# design.net
KiCad netlist of a schematic drawn in Altium Designer
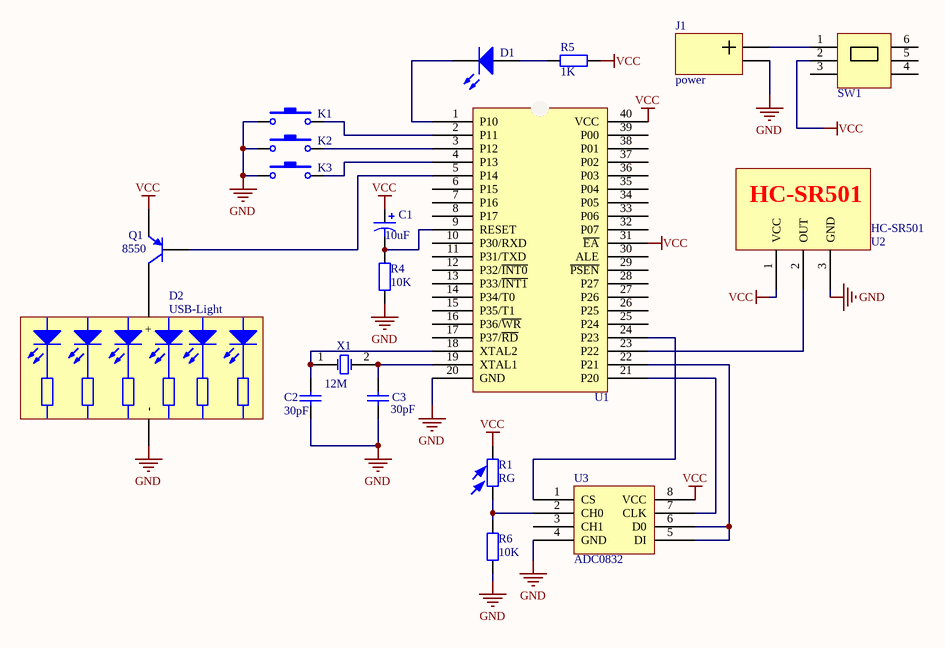
[diagram p0: 原理图.SCHDOC]

(export (version "E")
  (design (tool "Eeschema 10.0.6"))
  (components
    (comp (ref "C1") (value "10uF") (footprint "CAP_2") (libsource (lib "Schlib") (part "CAP_2")))
    (comp (ref "C2") (value "30pF") (footprint "CAP") (libsource (lib "Schlib") (part "CAP")))
    (comp (ref "C3") (value "30pF") (footprint "CAP") (libsource (lib "Schlib") (part "CAP")))
    (comp (ref "D1") (value "~") (footprint "LED") (libsource (lib "MANUAL") (part "LED")))
    (comp (ref "D2")
      (value "USB-Light")
      (footprint "USB-A - 2")
      (libsource (lib "MANUAL") (part "USB-Light"))
    )
    (comp (ref "J1") (value "power") (footprint "DC3.5") (libsource (lib "Schlib") (part "DC5.5")))
    (comp (ref "K1") (value "KEY") (footprint "KEY") (libsource (lib "Schlib") (part "KEY")))
    (comp (ref "K2") (value "KEY") (footprint "KEY") (libsource (lib "Schlib") (part "KEY")))
    (comp (ref "K3") (value "KEY") (footprint "KEY") (libsource (lib "Schlib") (part "KEY")))
    (comp (ref "Q1") (value "8550") (footprint "NPN") (libsource (lib "Schlib") (part "PNP")))
    (comp (ref "R1") (value "RG") (libsource (lib "MANUAL") (part "RG")))
    (comp (ref "R4") (value "10K") (footprint "RES") (libsource (lib "Schlib") (part "Res")))
    (comp (ref "R5") (value "1K") (footprint "RES") (libsource (lib "MANUAL") (part "Res")))
    (comp (ref "R6") (value "10K") (footprint "RES") (libsource (lib "") (part "Res_1")))
    (comp (ref "SW1") (value "SWT") (footprint "SWT") (libsource (lib "Schlib") (part "SWT")))
    (comp (ref "U1") (value "STC89C52") (footprint "DIP40") (libsource (lib "Schlib") (part "STC89C52")))
    (comp (ref "U2") (value "HC-SR501") (footprint "HC-SR501") (libsource (lib "MANUAL") (part "HC-SR501")))
    (comp (ref "U3") (value "ADC0832") (footprint "DIP8") (libsource (lib "MANUAL") (part "ADC0832")))
    (comp (ref "X1") (value "12M") (footprint "XTAL") (libsource (lib "Schlib") (part "XTAL")))
  )
  (nets
    (net (code "1") (name "GND") (class "Default")
      (node (ref "C2") (pin "1") (pinfunction "1_1") (pintype "passive"))
      (node (ref "C3") (pin "1") (pinfunction "1_1") (pintype "passive"))
      (node (ref "D2") (pin "2") (pinfunction "-_2") (pintype "passive"))
      (node (ref "J1") (pin "2") (pinfunction "2_2") (pintype "passive"))
      (node (ref "K1") (pin "1") (pinfunction "1_1") (pintype "passive"))
      (node (ref "K2") (pin "1") (pinfunction "1_1") (pintype "passive"))
      (node (ref "K3") (pin "1") (pinfunction "1_1") (pintype "passive"))
      (node (ref "R4") (pin "1") (pinfunction "1_1") (pintype "passive"))
      (node (ref "R6") (pin "1") (pinfunction "1_1") (pintype "passive"))
      (node (ref "U1") (pin "20") (pinfunction "GND_20") (pintype "passive"))
      (node (ref "U2") (pin "3") (pinfunction "GND_3") (pintype "passive"))
      (node (ref "U3") (pin "4") (pinfunction "GND_4") (pintype "passive"))
    )
    (net (code "2") (name "Net-(D1-Pad1)") (class "Default")
      (node (ref "D1") (pin "1") (pinfunction "1_1") (pintype "passive"))
      (node (ref "R5") (pin "1") (pinfunction "1_1") (pintype "passive"))
    )
    (net (code "3") (name "Net-(D2-+)") (class "Default")
      (node (ref "D2") (pin "1") (pinfunction "+_1") (pintype "passive"))
      (node (ref "Q1") (pin "C") (pinfunction "C_C") (pintype "passive"))
    )
    (net (code "4") (name "Net-(SW1-0)") (class "Default")
      (node (ref "J1") (pin "1") (pinfunction "1_1") (pintype "passive"))
      (node (ref "SW1") (pin "1") (pinfunction "0_1") (pintype "passive"))
    )
    (net (code "5") (name "Net-(U1-P10)") (class "Default")
      (node (ref "D1") (pin "2") (pinfunction "2_2") (pintype "passive"))
      (node (ref "U1") (pin "1") (pinfunction "P10_1") (pintype "passive"))
    )
    (net (code "6") (name "Net-(U1-P11)") (class "Default")
      (node (ref "K1") (pin "2") (pinfunction "2_2") (pintype "passive"))
      (node (ref "U1") (pin "2") (pinfunction "P11_2") (pintype "passive"))
    )
    (net (code "7") (name "Net-(U1-P12)") (class "Default")
      (node (ref "K2") (pin "2") (pinfunction "2_2") (pintype "passive"))
      (node (ref "U1") (pin "3") (pinfunction "P12_3") (pintype "passive"))
    )
    (net (code "8") (name "Net-(U1-P13)") (class "Default")
      (node (ref "K3") (pin "2") (pinfunction "2_2") (pintype "passive"))
      (node (ref "U1") (pin "4") (pinfunction "P13_4") (pintype "passive"))
    )
    (net (code "9") (name "Net-(U1-P14)") (class "Default")
      (node (ref "Q1") (pin "B") (pinfunction "B_B") (pintype "passive"))
      (node (ref "U1") (pin "5") (pinfunction "P14_5") (pintype "passive"))
    )
    (net (code "10") (name "Net-(U1-P20)") (class "Default")
      (node (ref "U1") (pin "21") (pinfunction "P20_21") (pintype "passive"))
      (node (ref "U3") (pin "7") (pinfunction "CLK_7") (pintype "passive"))
    )
    (net (code "11") (name "Net-(U1-P21)") (class "Default")
      (node (ref "U1") (pin "22") (pinfunction "P21_22") (pintype "passive"))
      (node (ref "U3") (pin "5") (pinfunction "DI_5") (pintype "passive"))
      (node (ref "U3") (pin "6") (pinfunction "D0_6") (pintype "passive"))
    )
    (net (code "12") (name "Net-(U1-P22)") (class "Default")
      (node (ref "U1") (pin "23") (pinfunction "P22_23") (pintype "passive"))
      (node (ref "U2") (pin "2") (pinfunction "OUT_2") (pintype "passive"))
    )
    (net (code "13") (name "Net-(U1-P23)") (class "Default")
      (node (ref "U1") (pin "24") (pinfunction "P23_24") (pintype "passive"))
      (node (ref "U3") (pin "1") (pinfunction "CS_1") (pintype "passive"))
    )
    (net (code "14") (name "Net-(U1-RESET)") (class "Default")
      (node (ref "C1") (pin "2") (pinfunction "2_2") (pintype "passive"))
      (node (ref "R4") (pin "2") (pinfunction "2_2") (pintype "passive"))
      (node (ref "U1") (pin "9") (pinfunction "RESET_9") (pintype "passive"))
    )
    (net (code "15") (name "Net-(U1-XTAL1)") (class "Default")
      (node (ref "C3") (pin "2") (pinfunction "2_2") (pintype "passive"))
      (node (ref "U1") (pin "19") (pinfunction "XTAL1_19") (pintype "passive"))
      (node (ref "X1") (pin "2") (pinfunction "OSC2_2") (pintype "passive"))
    )
    (net (code "16") (name "Net-(U1-XTAL2)") (class "Default")
      (node (ref "C2") (pin "2") (pinfunction "2_2") (pintype "passive"))
      (node (ref "U1") (pin "18") (pinfunction "XTAL2_18") (pintype "passive"))
      (node (ref "X1") (pin "1") (pinfunction "OSC1_1") (pintype "passive"))
    )
    (net (code "17") (name "Net-(U3-CH0)") (class "Default")
      (node (ref "R1") (pin "1") (pinfunction "1_1") (pintype "passive"))
      (node (ref "R6") (pin "2") (pinfunction "2_2") (pintype "passive"))
      (node (ref "U3") (pin "2") (pinfunction "CH0_2") (pintype "passive"))
    )
    (net (code "18") (name "VCC") (class "Default")
      (node (ref "C1") (pin "1") (pinfunction "1_1") (pintype "passive"))
      (node (ref "Q1") (pin "E") (pinfunction "E_E") (pintype "passive"))
      (node (ref "R1") (pin "2") (pinfunction "2_2") (pintype "passive"))
      (node (ref "R5") (pin "2") (pinfunction "2_2") (pintype "passive"))
      (node (ref "SW1") (pin "2") (pinfunction "1_2") (pintype "passive"))
      (node (ref "U1") (pin "31") (pinfunction "~{EA}_31") (pintype "passive"))
      (node (ref "U1") (pin "40") (pinfunction "VCC_40") (pintype "passive"))
      (node (ref "U2") (pin "1") (pinfunction "VCC_1") (pintype "passive"))
      (node (ref "U3") (pin "8") (pinfunction "VCC_8") (pintype "passive"))
    )
    (net (code "19") (name "unconnected-(SW1-2-Pad3)") (class "Default")
      (node (ref "SW1") (pin "3") (pinfunction "2_3") (pintype "passive"))
    )
    (net (code "20") (name "unconnected-(SW1-3-Pad4)") (class "Default")
      (node (ref "SW1") (pin "4") (pinfunction "3_4") (pintype "passive"))
    )
    (net (code "21") (name "unconnected-(SW1-4-Pad5)") (class "Default")
      (node (ref "SW1") (pin "5") (pinfunction "4_5") (pintype "passive"))
    )
    (net (code "22") (name "unconnected-(SW1-5-Pad6)") (class "Default")
      (node (ref "SW1") (pin "6") (pinfunction "5_6") (pintype "passive"))
    )
    (net (code "23") (name "unconnected-(U1-ALE-Pad30)") (class "Default")
      (node (ref "U1") (pin "30") (pinfunction "ALE_30") (pintype "passive"))
    )
    (net (code "24") (name "unconnected-(U1-P00-Pad39)") (class "Default")
      (node (ref "U1") (pin "39") (pinfunction "P00_39") (pintype "passive"))
    )
    (net (code "25") (name "unconnected-(U1-P01-Pad38)") (class "Default")
      (node (ref "U1") (pin "38") (pinfunction "P01_38") (pintype "passive"))
    )
    (net (code "26") (name "unconnected-(U1-P02-Pad37)") (class "Default")
      (node (ref "U1") (pin "37") (pinfunction "P02_37") (pintype "passive"))
    )
    (net (code "27") (name "unconnected-(U1-P03-Pad36)") (class "Default")
      (node (ref "U1") (pin "36") (pinfunction "P03_36") (pintype "passive"))
    )
    (net (code "28") (name "unconnected-(U1-P04-Pad35)") (class "Default")
      (node (ref "U1") (pin "35") (pinfunction "P04_35") (pintype "passive"))
    )
    (net (code "29") (name "unconnected-(U1-P05-Pad34)") (class "Default")
      (node (ref "U1") (pin "34") (pinfunction "P05_34") (pintype "passive"))
    )
    (net (code "30") (name "unconnected-(U1-P06-Pad33)") (class "Default")
      (node (ref "U1") (pin "33") (pinfunction "P06_33") (pintype "passive"))
    )
    (net (code "31") (name "unconnected-(U1-P07-Pad32)") (class "Default")
      (node (ref "U1") (pin "32") (pinfunction "P07_32") (pintype "passive"))
    )
    (net (code "32") (name "unconnected-(U1-P15-Pad6)") (class "Default")
      (node (ref "U1") (pin "6") (pinfunction "P15_6") (pintype "passive"))
    )
    (net (code "33") (name "unconnected-(U1-P16-Pad7)") (class "Default")
      (node (ref "U1") (pin "7") (pinfunction "P16_7") (pintype "passive"))
    )
    (net (code "34") (name "unconnected-(U1-P17-Pad8)") (class "Default")
      (node (ref "U1") (pin "8") (pinfunction "P17_8") (pintype "passive"))
    )
    (net (code "35") (name "unconnected-(U1-P24-Pad25)") (class "Default")
      (node (ref "U1") (pin "25") (pinfunction "P24_25") (pintype "passive"))
    )
    (net (code "36") (name "unconnected-(U1-P25-Pad26)") (class "Default")
      (node (ref "U1") (pin "26") (pinfunction "P25_26") (pintype "passive"))
    )
    (net (code "37") (name "unconnected-(U1-P26-Pad27)") (class "Default")
      (node (ref "U1") (pin "27") (pinfunction "P26_27") (pintype "passive"))
    )
    (net (code "38") (name "unconnected-(U1-P27-Pad28)") (class "Default")
      (node (ref "U1") (pin "28") (pinfunction "P27_28") (pintype "passive"))
    )
    (net (code "39") (name "unconnected-(U1-P30{slash}RXD-Pad10)") (class "Default")
      (node (ref "U1") (pin "10") (pinfunction "P30/RXD_10") (pintype "passive"))
    )
    (net (code "40") (name "unconnected-(U1-P31{slash}TXD-Pad11)") (class "Default")
      (node (ref "U1") (pin "11") (pinfunction "P31/TXD_11") (pintype "passive"))
    )
    (net (code "41") (name "unconnected-(U1-P32{slash}~{INT0}-Pad12)") (class "Default")
      (node (ref "U1") (pin "12") (pinfunction "P32/~{INT0}_12") (pintype "passive"))
    )
    (net (code "42") (name "unconnected-(U1-P33{slash}~{INT1}-Pad13)") (class "Default")
      (node (ref "U1") (pin "13") (pinfunction "P33/~{INT1}_13") (pintype "passive"))
    )
    (net (code "43") (name "unconnected-(U1-P34{slash}T0-Pad14)") (class "Default")
      (node (ref "U1") (pin "14") (pinfunction "P34/T0_14") (pintype "passive"))
    )
    (net (code "44") (name "unconnected-(U1-P35{slash}T1-Pad15)") (class "Default")
      (node (ref "U1") (pin "15") (pinfunction "P35/T1_15") (pintype "passive"))
    )
    (net (code "45") (name "unconnected-(U1-P36{slash}~{WR}-Pad16)") (class "Default")
      (node (ref "U1") (pin "16") (pinfunction "P36/~{WR}_16") (pintype "passive"))
    )
    (net (code "46") (name "unconnected-(U1-P37{slash}~{RD}-Pad17)") (class "Default")
      (node (ref "U1") (pin "17") (pinfunction "P37/~{RD}_17") (pintype "passive"))
    )
    (net (code "47") (name "unconnected-(U1-~{PSEN}-Pad29)") (class "Default")
      (node (ref "U1") (pin "29") (pinfunction "~{PSEN}_29") (pintype "passive"))
    )
    (net (code "48") (name "unconnected-(U3-CH1-Pad3)") (class "Default")
      (node (ref "U3") (pin "3") (pinfunction "CH1_3") (pintype "passive"))
    )
  )
)
